# Expander.net
KiCad netlist of a schematic drawn in Altium Designer
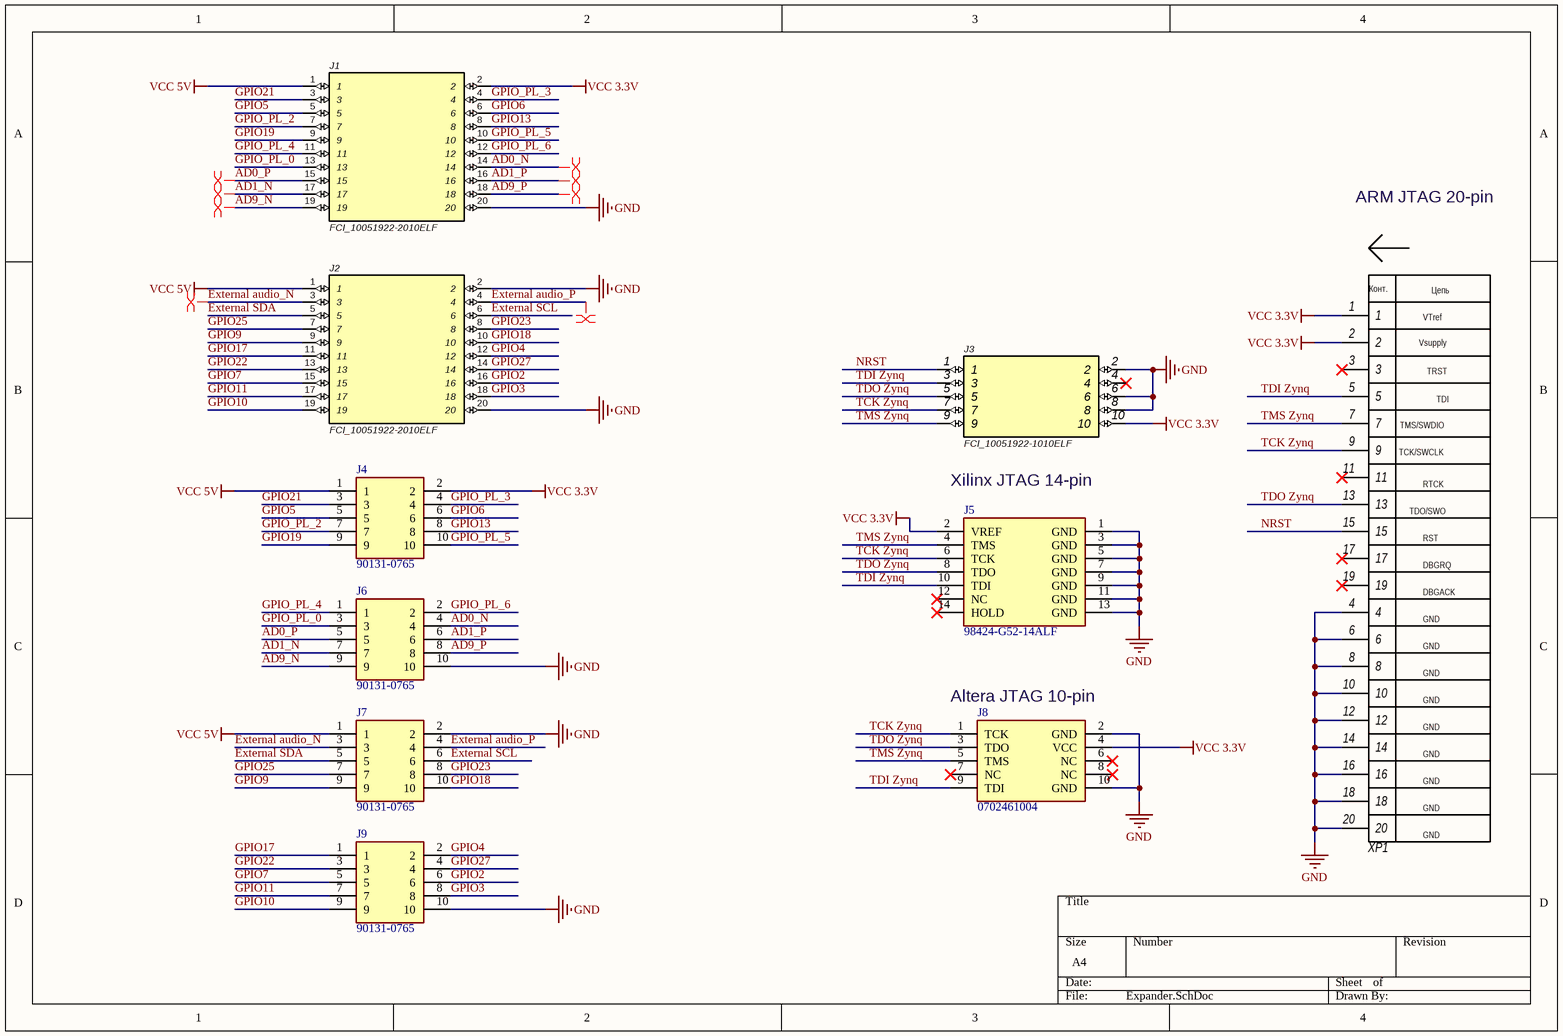
[diagram p0: Expander.SchDoc]

(export (version "E")
  (design (tool "Eeschema 10.0.6"))
  (components
    (comp (ref "J1")
      (value "FCI_10051922-2010ELF")
      (footprint "*FCI_10051922-2010ELF")
      (description "0.50mm FFC/FPC Connectors 20CKT RA SMT ZIF CON BOTTOM CONTACT")
      (libsource (lib "Expander") (part "FCI_10051922-2010ELF"))
    )
    (comp (ref "J2")
      (value "FCI_10051922-2010ELF")
      (footprint "*FCI_10051922-2010ELF")
      (description "0.50mm FFC/FPC Connectors 20CKT RA SMT ZIF CON BOTTOM CONTACT")
      (libsource (lib "Expander") (part "FCI_10051922-2010ELF"))
    )
    (comp (ref "J3")
      (value "FCI_10051922-1010ELF")
      (footprint "*FCI_10051922-1010ELF")
      (description "0.50mm FFC/FPC Connectors 10CKT RA SMT ZIF CON BOTTOM CONTACT")
      (libsource (lib "Expander") (part "FCI_10051922-1010ELF"))
    )
    (comp (ref "J4")
      (value "90131-0765")
      (footprint "HDRV10W90P254_2X5_1260X500X560P")
      (description "Connector")
      (fields (field (name "MOUSER PART NUMBER") "538-90131-0765") (field (name "RS PART NUMBER") "3606471P"))
      (libsource (lib "Expander") (part "90131-0765"))
    )
    (comp (ref "J5")
      (value "98424-G52-14ALF")
      (footprint "98424G5214ALF")
      (description "Connector")
      (fields
        (field (name "MOUSER PART NUMBER") "649-98424-G52-14ALF")
        (field (name "RS PART NUMBER") "1822960")
      )
      (libsource (lib "Expander") (part "98424-G52-14ALF"))
    )
    (comp (ref "J6")
      (value "90131-0765")
      (footprint "HDRV10W90P254_2X5_1260X500X560P")
      (description "Connector")
      (fields (field (name "MOUSER PART NUMBER") "538-90131-0765") (field (name "RS PART NUMBER") "3606471P"))
      (libsource (lib "Expander") (part "90131-0765"))
    )
    (comp (ref "J7")
      (value "90131-0765")
      (footprint "HDRV10W90P254_2X5_1260X500X560P")
      (description "Connector")
      (fields (field (name "MOUSER PART NUMBER") "538-90131-0765") (field (name "RS PART NUMBER") "3606471P"))
      (libsource (lib "Expander") (part "90131-0765"))
    )
    (comp (ref "J8")
      (value "0702461004")
      (footprint "SamacSys:SHDR10W99P254_2X5_2032X889X947P")
      (description "Connector")
      (libsource (lib "Expander") (part "0702461004"))
    )
    (comp (ref "J9")
      (value "90131-0765")
      (footprint "HDRV10W90P254_2X5_1260X500X560P")
      (description "Connector")
      (fields (field (name "MOUSER PART NUMBER") "538-90131-0765") (field (name "RS PART NUMBER") "3606471P"))
      (libsource (lib "Expander") (part "90131-0765"))
    )
    (comp (ref "XP1")
      (value "BH-20")
      (footprint "BH-20")
      (description "JTAG")
      (libsource (lib "Expander") (part "BH-20"))
    )
  )
  (nets
    (net (code "1") (name "/AD0_N") (class "Default")
      (node (ref "J1") (pin "14") (pinfunction "14_14") (pintype "bidirectional"))
      (node (ref "J6") (pin "4") (pinfunction "4_4") (pintype "passive"))
    )
    (net (code "2") (name "/AD0_P") (class "Default")
      (node (ref "J1") (pin "15") (pinfunction "15_15") (pintype "bidirectional"))
      (node (ref "J6") (pin "5") (pinfunction "5_5") (pintype "passive"))
    )
    (net (code "3") (name "/AD1_N") (class "Default")
      (node (ref "J1") (pin "17") (pinfunction "17_17") (pintype "bidirectional"))
      (node (ref "J6") (pin "7") (pinfunction "7_7") (pintype "passive"))
    )
    (net (code "4") (name "/AD1_P") (class "Default")
      (node (ref "J1") (pin "16") (pinfunction "16_16") (pintype "bidirectional"))
      (node (ref "J6") (pin "6") (pinfunction "6_6") (pintype "passive"))
    )
    (net (code "5") (name "/AD9_N") (class "Default")
      (node (ref "J1") (pin "19") (pinfunction "19_19") (pintype "bidirectional"))
      (node (ref "J6") (pin "9") (pinfunction "9_9") (pintype "passive"))
    )
    (net (code "6") (name "/AD9_P") (class "Default")
      (node (ref "J1") (pin "18") (pinfunction "18_18") (pintype "bidirectional"))
      (node (ref "J6") (pin "8") (pinfunction "8_8") (pintype "passive"))
    )
    (net (code "7") (name "/External SCL") (class "Default")
      (node (ref "J2") (pin "6") (pinfunction "6_6") (pintype "bidirectional"))
      (node (ref "J7") (pin "6") (pinfunction "6_6") (pintype "passive"))
    )
    (net (code "8") (name "/External SDA") (class "Default")
      (node (ref "J2") (pin "5") (pinfunction "5_5") (pintype "bidirectional"))
      (node (ref "J7") (pin "5") (pinfunction "5_5") (pintype "passive"))
    )
    (net (code "9") (name "/External audio_N") (class "Default")
      (node (ref "J2") (pin "3") (pinfunction "3_3") (pintype "bidirectional"))
      (node (ref "J7") (pin "3") (pinfunction "3_3") (pintype "passive"))
    )
    (net (code "10") (name "/External audio_P") (class "Default")
      (node (ref "J2") (pin "4") (pinfunction "4_4") (pintype "bidirectional"))
      (node (ref "J7") (pin "4") (pinfunction "4_4") (pintype "passive"))
    )
    (net (code "11") (name "/GPIO2") (class "Default")
      (node (ref "J2") (pin "16") (pinfunction "16_16") (pintype "bidirectional"))
      (node (ref "J9") (pin "6") (pinfunction "6_6") (pintype "passive"))
    )
    (net (code "12") (name "/GPIO3") (class "Default")
      (node (ref "J2") (pin "18") (pinfunction "18_18") (pintype "bidirectional"))
      (node (ref "J9") (pin "8") (pinfunction "8_8") (pintype "passive"))
    )
    (net (code "13") (name "/GPIO4") (class "Default")
      (node (ref "J2") (pin "12") (pinfunction "12_12") (pintype "bidirectional"))
      (node (ref "J9") (pin "2") (pinfunction "2_2") (pintype "passive"))
    )
    (net (code "14") (name "/GPIO5") (class "Default")
      (node (ref "J1") (pin "5") (pinfunction "5_5") (pintype "bidirectional"))
      (node (ref "J4") (pin "5") (pinfunction "5_5") (pintype "passive"))
    )
    (net (code "15") (name "/GPIO6") (class "Default")
      (node (ref "J1") (pin "6") (pinfunction "6_6") (pintype "bidirectional"))
      (node (ref "J4") (pin "6") (pinfunction "6_6") (pintype "passive"))
    )
    (net (code "16") (name "/GPIO7") (class "Default")
      (node (ref "J2") (pin "15") (pinfunction "15_15") (pintype "bidirectional"))
      (node (ref "J9") (pin "5") (pinfunction "5_5") (pintype "passive"))
    )
    (net (code "17") (name "/GPIO9") (class "Default")
      (node (ref "J2") (pin "9") (pinfunction "9_9") (pintype "bidirectional"))
      (node (ref "J7") (pin "9") (pinfunction "9_9") (pintype "passive"))
    )
    (net (code "18") (name "/GPIO10") (class "Default")
      (node (ref "J2") (pin "19") (pinfunction "19_19") (pintype "bidirectional"))
      (node (ref "J9") (pin "9") (pinfunction "9_9") (pintype "passive"))
    )
    (net (code "19") (name "/GPIO11") (class "Default")
      (node (ref "J2") (pin "17") (pinfunction "17_17") (pintype "bidirectional"))
      (node (ref "J9") (pin "7") (pinfunction "7_7") (pintype "passive"))
    )
    (net (code "20") (name "/GPIO13") (class "Default")
      (node (ref "J1") (pin "8") (pinfunction "8_8") (pintype "bidirectional"))
      (node (ref "J4") (pin "8") (pinfunction "8_8") (pintype "passive"))
    )
    (net (code "21") (name "/GPIO17") (class "Default")
      (node (ref "J2") (pin "11") (pinfunction "11_11") (pintype "bidirectional"))
      (node (ref "J9") (pin "1") (pinfunction "1_1") (pintype "passive"))
    )
    (net (code "22") (name "/GPIO18") (class "Default")
      (node (ref "J2") (pin "10") (pinfunction "10_10") (pintype "bidirectional"))
      (node (ref "J7") (pin "10") (pinfunction "10_10") (pintype "passive"))
    )
    (net (code "23") (name "/GPIO19") (class "Default")
      (node (ref "J1") (pin "9") (pinfunction "9_9") (pintype "bidirectional"))
      (node (ref "J4") (pin "9") (pinfunction "9_9") (pintype "passive"))
    )
    (net (code "24") (name "/GPIO21") (class "Default")
      (node (ref "J1") (pin "3") (pinfunction "3_3") (pintype "bidirectional"))
      (node (ref "J4") (pin "3") (pinfunction "3_3") (pintype "passive"))
    )
    (net (code "25") (name "/GPIO22") (class "Default")
      (node (ref "J2") (pin "13") (pinfunction "13_13") (pintype "bidirectional"))
      (node (ref "J9") (pin "3") (pinfunction "3_3") (pintype "passive"))
    )
    (net (code "26") (name "/GPIO23") (class "Default")
      (node (ref "J2") (pin "8") (pinfunction "8_8") (pintype "bidirectional"))
      (node (ref "J7") (pin "8") (pinfunction "8_8") (pintype "passive"))
    )
    (net (code "27") (name "/GPIO25") (class "Default")
      (node (ref "J2") (pin "7") (pinfunction "7_7") (pintype "bidirectional"))
      (node (ref "J7") (pin "7") (pinfunction "7_7") (pintype "passive"))
    )
    (net (code "28") (name "/GPIO27") (class "Default")
      (node (ref "J2") (pin "14") (pinfunction "14_14") (pintype "bidirectional"))
      (node (ref "J9") (pin "4") (pinfunction "4_4") (pintype "passive"))
    )
    (net (code "29") (name "/GPIO_PL_0") (class "Default")
      (node (ref "J1") (pin "13") (pinfunction "13_13") (pintype "bidirectional"))
      (node (ref "J6") (pin "3") (pinfunction "3_3") (pintype "passive"))
    )
    (net (code "30") (name "/GPIO_PL_2") (class "Default")
      (node (ref "J1") (pin "7") (pinfunction "7_7") (pintype "bidirectional"))
      (node (ref "J4") (pin "7") (pinfunction "7_7") (pintype "passive"))
    )
    (net (code "31") (name "/GPIO_PL_3") (class "Default")
      (node (ref "J1") (pin "4") (pinfunction "4_4") (pintype "bidirectional"))
      (node (ref "J4") (pin "4") (pinfunction "4_4") (pintype "passive"))
    )
    (net (code "32") (name "/GPIO_PL_4") (class "Default")
      (node (ref "J1") (pin "11") (pinfunction "11_11") (pintype "bidirectional"))
      (node (ref "J6") (pin "1") (pinfunction "1_1") (pintype "passive"))
    )
    (net (code "33") (name "/GPIO_PL_5") (class "Default")
      (node (ref "J1") (pin "10") (pinfunction "10_10") (pintype "bidirectional"))
      (node (ref "J4") (pin "10") (pinfunction "10_10") (pintype "passive"))
    )
    (net (code "34") (name "/GPIO_PL_6") (class "Default")
      (node (ref "J1") (pin "12") (pinfunction "12_12") (pintype "bidirectional"))
      (node (ref "J6") (pin "2") (pinfunction "2_2") (pintype "passive"))
    )
    (net (code "35") (name "/NRST") (class "Default")
      (node (ref "J3") (pin "1") (pinfunction "1_1") (pintype "bidirectional"))
      (node (ref "XP1") (pin "15") (pinfunction "15_15") (pintype "passive"))
    )
    (net (code "36") (name "/TCK Zynq") (class "Default")
      (node (ref "J3") (pin "7") (pinfunction "7_7") (pintype "bidirectional"))
      (node (ref "J5") (pin "6") (pinfunction "TCK_6") (pintype "passive"))
      (node (ref "J8") (pin "1") (pinfunction "TCK_1") (pintype "passive"))
      (node (ref "XP1") (pin "9") (pinfunction "9_9") (pintype "passive"))
    )
    (net (code "37") (name "/TDI Zynq") (class "Default")
      (node (ref "J3") (pin "3") (pinfunction "3_3") (pintype "bidirectional"))
      (node (ref "J5") (pin "10") (pinfunction "TDI_10") (pintype "passive"))
      (node (ref "J8") (pin "9") (pinfunction "TDI_9") (pintype "passive"))
      (node (ref "XP1") (pin "5") (pinfunction "5_5") (pintype "passive"))
    )
    (net (code "38") (name "/TDO Zynq") (class "Default")
      (node (ref "J3") (pin "5") (pinfunction "5_5") (pintype "bidirectional"))
      (node (ref "J5") (pin "8") (pinfunction "TDO_8") (pintype "passive"))
      (node (ref "J8") (pin "3") (pinfunction "TDO_3") (pintype "passive"))
      (node (ref "XP1") (pin "13") (pinfunction "13_13") (pintype "passive"))
    )
    (net (code "39") (name "/TMS Zynq") (class "Default")
      (node (ref "J3") (pin "9") (pinfunction "9_9") (pintype "bidirectional"))
      (node (ref "J5") (pin "4") (pinfunction "TMS_4") (pintype "passive"))
      (node (ref "J8") (pin "5") (pinfunction "TMS_5") (pintype "passive"))
      (node (ref "XP1") (pin "7") (pinfunction "7_7") (pintype "passive"))
    )
    (net (code "40") (name "GND") (class "Default")
      (node (ref "J1") (pin "20") (pinfunction "20_20") (pintype "bidirectional"))
      (node (ref "J2") (pin "2") (pinfunction "2_2") (pintype "bidirectional"))
      (node (ref "J2") (pin "20") (pinfunction "20_20") (pintype "bidirectional"))
      (node (ref "J3") (pin "2") (pinfunction "2_2") (pintype "bidirectional"))
      (node (ref "J3") (pin "6") (pinfunction "6_6") (pintype "bidirectional"))
      (node (ref "J3") (pin "8") (pinfunction "8_8") (pintype "bidirectional"))
      (node (ref "J5") (pin "1") (pinfunction "GND_1") (pintype "passive"))
      (node (ref "J5") (pin "11") (pinfunction "GND_11") (pintype "passive"))
      (node (ref "J5") (pin "13") (pinfunction "GND_13") (pintype "passive"))
      (node (ref "J5") (pin "3") (pinfunction "GND_3") (pintype "passive"))
      (node (ref "J5") (pin "5") (pinfunction "GND_5") (pintype "passive"))
      (node (ref "J5") (pin "7") (pinfunction "GND_7") (pintype "passive"))
      (node (ref "J5") (pin "9") (pinfunction "GND_9") (pintype "passive"))
      (node (ref "J6") (pin "10") (pinfunction "10_10") (pintype "passive"))
      (node (ref "J7") (pin "2") (pinfunction "2_2") (pintype "passive"))
      (node (ref "J8") (pin "10") (pinfunction "GND_10") (pintype "passive"))
      (node (ref "J8") (pin "2") (pinfunction "GND_2") (pintype "passive"))
      (node (ref "J9") (pin "10") (pinfunction "10_10") (pintype "passive"))
      (node (ref "XP1") (pin "10") (pinfunction "10_10") (pintype "passive"))
      (node (ref "XP1") (pin "12") (pinfunction "12_12") (pintype "passive"))
      (node (ref "XP1") (pin "14") (pinfunction "14_14") (pintype "passive"))
      (node (ref "XP1") (pin "16") (pinfunction "16_16") (pintype "passive"))
      (node (ref "XP1") (pin "18") (pinfunction "18_18") (pintype "passive"))
      (node (ref "XP1") (pin "20") (pinfunction "20_20") (pintype "passive"))
      (node (ref "XP1") (pin "4") (pinfunction "4_4") (pintype "passive"))
      (node (ref "XP1") (pin "6") (pinfunction "6_6") (pintype "passive"))
      (node (ref "XP1") (pin "8") (pinfunction "8_8") (pintype "passive"))
    )
    (net (code "41") (name "VCC 3.3V") (class "Default")
      (node (ref "J1") (pin "2") (pinfunction "2_2") (pintype "bidirectional"))
      (node (ref "J3") (pin "10") (pinfunction "10_10") (pintype "bidirectional"))
      (node (ref "J4") (pin "2") (pinfunction "2_2") (pintype "passive"))
      (node (ref "J5") (pin "2") (pinfunction "VREF_2") (pintype "passive"))
      (node (ref "J8") (pin "4") (pinfunction "VCC_4") (pintype "passive"))
      (node (ref "XP1") (pin "1") (pinfunction "1_1") (pintype "passive"))
      (node (ref "XP1") (pin "2") (pinfunction "2_2") (pintype "passive"))
    )
    (net (code "42") (name "VCC 5V") (class "Default")
      (node (ref "J1") (pin "1") (pinfunction "1_1") (pintype "bidirectional"))
      (node (ref "J2") (pin "1") (pinfunction "1_1") (pintype "bidirectional"))
      (node (ref "J4") (pin "1") (pinfunction "1_1") (pintype "passive"))
      (node (ref "J7") (pin "1") (pinfunction "1_1") (pintype "passive"))
    )
    (net (code "43") (name "unconnected-(J3-Pad4)") (class "Default")
      (node (ref "J3") (pin "4") (pinfunction "4_4") (pintype "bidirectional+no_connect"))
    )
    (net (code "44") (name "unconnected-(J5-HOLD-Pad14)") (class "Default")
      (node (ref "J5") (pin "14") (pinfunction "HOLD_14") (pintype "passive+no_connect"))
    )
    (net (code "45") (name "unconnected-(J5-NC-Pad12)") (class "Default")
      (node (ref "J5") (pin "12") (pinfunction "NC_12") (pintype "passive+no_connect"))
    )
    (net (code "46") (name "unconnected-(J8-NC-Pad6)") (class "Default")
      (node (ref "J8") (pin "6") (pinfunction "NC_6") (pintype "passive+no_connect"))
    )
    (net (code "47") (name "unconnected-(J8-NC-Pad7)") (class "Default")
      (node (ref "J8") (pin "7") (pinfunction "NC_7") (pintype "passive+no_connect"))
    )
    (net (code "48") (name "unconnected-(J8-NC-Pad8)") (class "Default")
      (node (ref "J8") (pin "8") (pinfunction "NC_8") (pintype "passive+no_connect"))
    )
    (net (code "49") (name "unconnected-(XP1-Pad3)") (class "Default")
      (node (ref "XP1") (pin "3") (pinfunction "3_3") (pintype "passive+no_connect"))
    )
    (net (code "50") (name "unconnected-(XP1-Pad11)") (class "Default")
      (node (ref "XP1") (pin "11") (pinfunction "11_11") (pintype "passive+no_connect"))
    )
    (net (code "51") (name "unconnected-(XP1-Pad17)") (class "Default")
      (node (ref "XP1") (pin "17") (pinfunction "17_17") (pintype "passive+no_connect"))
    )
    (net (code "52") (name "unconnected-(XP1-Pad19)") (class "Default")
      (node (ref "XP1") (pin "19") (pinfunction "19_19") (pintype "passive+no_connect"))
    )
  )
)
